# VFD_PSU_V2.net
KiCad netlist of a schematic drawn in EAGLE
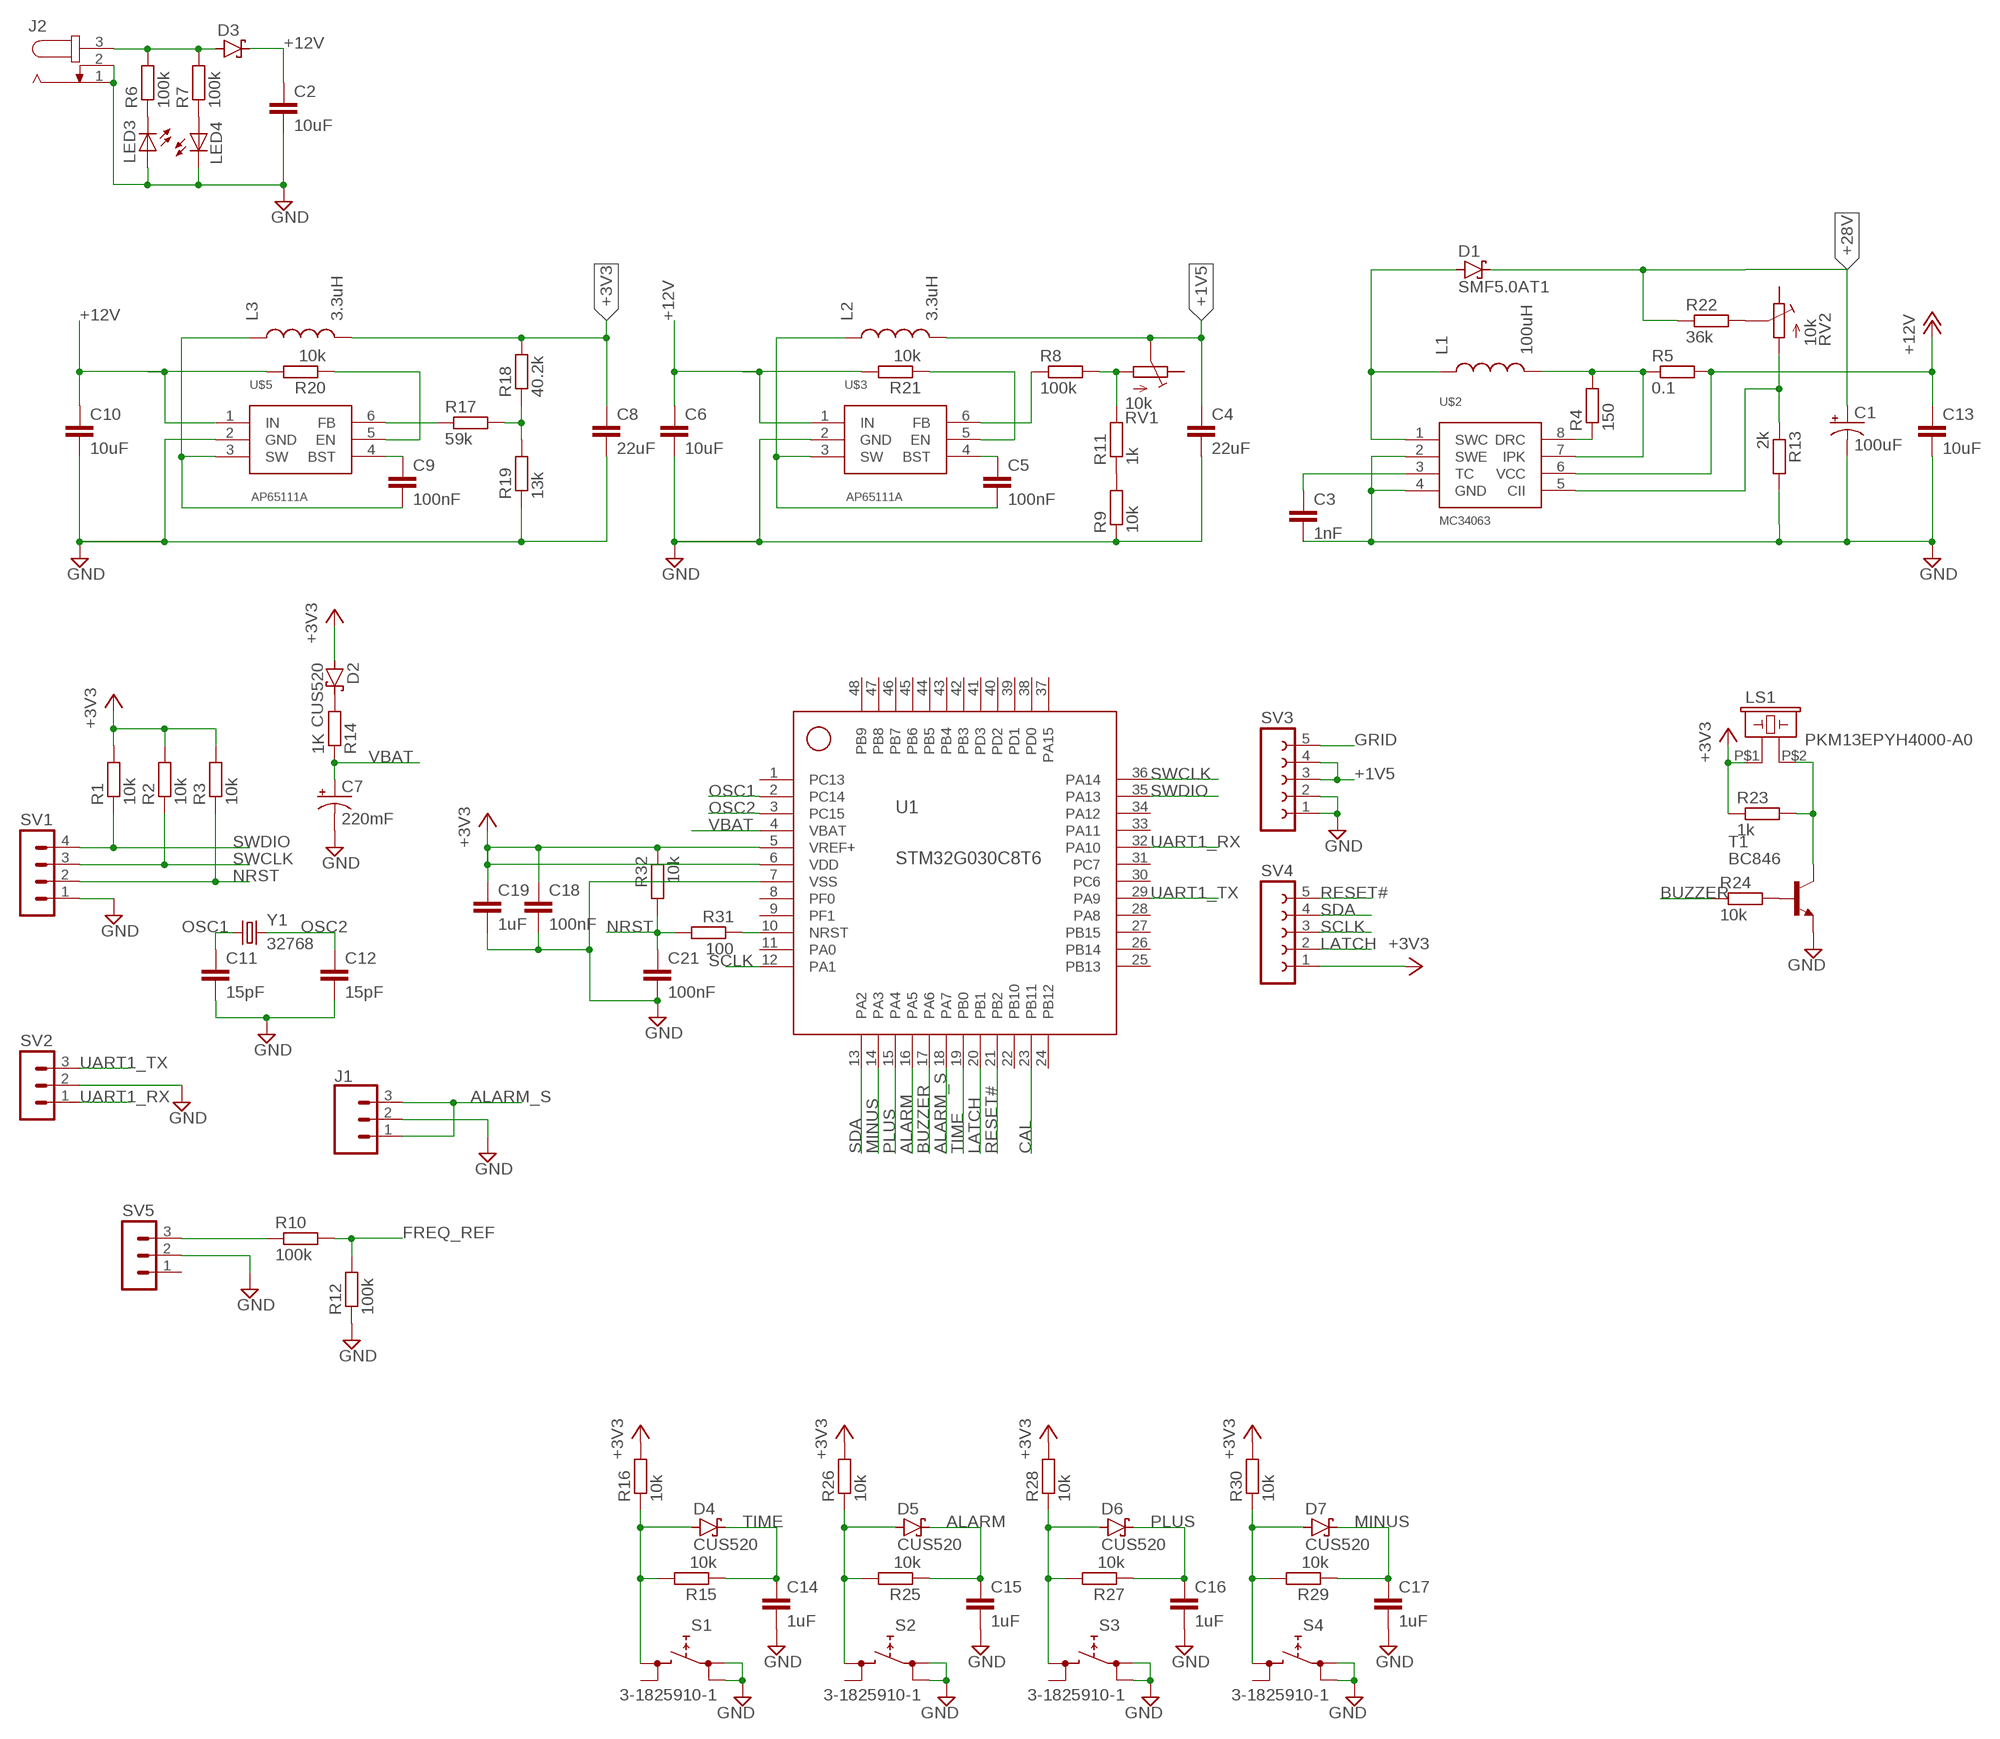
[diagram p0: schematic, sheet 1]

(export (version "E")
  (design (tool "Eeschema 10.0.6"))
  (components
    (comp (ref "C1")
      (value "100uF")
      (footprint "eagle-import:PANASONIC_C")
      (libsource (lib "eagle-import") (part "22UF-POLAR-PANASONIC_C-35V-20%"))
    )
    (comp (ref "C2")
      (value "10uF")
      (footprint "eagle-import:C0805")
      (libsource (lib "eagle-import") (part "C-EUC0805"))
    )
    (comp (ref "C3")
      (value "1nF")
      (footprint "eagle-import:C0603")
      (libsource (lib "eagle-import") (part "C-EUC0603"))
    )
    (comp (ref "C4")
      (value "22uF")
      (footprint "eagle-import:C0805")
      (libsource (lib "eagle-import") (part "C-EUC0805"))
    )
    (comp (ref "C5")
      (value "100nF")
      (footprint "eagle-import:C0603")
      (libsource (lib "eagle-import") (part "C-EUC0603"))
    )
    (comp (ref "C6")
      (value "10uF")
      (footprint "eagle-import:C0805")
      (libsource (lib "eagle-import") (part "C-EUC0805"))
    )
    (comp (ref "C7")
      (value "220mF")
      (footprint "eagle-import:4.8-COINCELL-SCAP")
      (libsource (lib "eagle-import") (part "DSK-3R3H224U-HL"))
    )
    (comp (ref "C8")
      (value "22uF")
      (footprint "eagle-import:C0805")
      (libsource (lib "eagle-import") (part "C-EUC0805"))
    )
    (comp (ref "C9")
      (value "100nF")
      (footprint "eagle-import:C0603")
      (libsource (lib "eagle-import") (part "C-EUC0603"))
    )
    (comp (ref "C10")
      (value "10uF")
      (footprint "eagle-import:C0805")
      (libsource (lib "eagle-import") (part "C-EUC0805"))
    )
    (comp (ref "C11")
      (value "15pF")
      (footprint "eagle-import:C0402")
      (libsource (lib "eagle-import") (part "resistor_348_C-EUC0402"))
    )
    (comp (ref "C12")
      (value "15pF")
      (footprint "eagle-import:C0402")
      (libsource (lib "eagle-import") (part "resistor_348_C-EUC0402"))
    )
    (comp (ref "C13")
      (value "10uF")
      (footprint "eagle-import:C0805")
      (libsource (lib "eagle-import") (part "C-EUC0805"))
    )
    (comp (ref "C14")
      (value "1uF")
      (footprint "eagle-import:C0603")
      (libsource (lib "eagle-import") (part "C-EUC0603"))
    )
    (comp (ref "C15")
      (value "1uF")
      (footprint "eagle-import:C0603")
      (libsource (lib "eagle-import") (part "C-EUC0603"))
    )
    (comp (ref "C16")
      (value "1uF")
      (footprint "eagle-import:C0603")
      (libsource (lib "eagle-import") (part "C-EUC0603"))
    )
    (comp (ref "C17")
      (value "1uF")
      (footprint "eagle-import:C0603")
      (libsource (lib "eagle-import") (part "C-EUC0603"))
    )
    (comp (ref "C18")
      (value "100nF")
      (footprint "eagle-import:C0603")
      (libsource (lib "eagle-import") (part "C-EUC0603"))
    )
    (comp (ref "C19")
      (value "1uF")
      (footprint "eagle-import:C0603")
      (libsource (lib "eagle-import") (part "C-EUC0603"))
    )
    (comp (ref "C21")
      (value "100nF")
      (footprint "eagle-import:C0603")
      (libsource (lib "eagle-import") (part "C-EUC0603"))
    )
    (comp (ref "D1")
      (value "SMF5.0AT1")
      (footprint "eagle-import:SOD123FL")
      (libsource (lib "eagle-import") (part "SMF5.0AT1"))
    )
    (comp (ref "D2")
      (value "CUS520")
      (footprint "eagle-import:SOD323_ST")
      (libsource (lib "eagle-import") (part "BAT60J"))
    )
    (comp (ref "D3")
      (value "SCHOTTKY-DIODESMD")
      (footprint "eagle-import:SMB")
      (libsource (lib "eagle-import") (part "SCHOTTKY-DIODESMD"))
    )
    (comp (ref "D4")
      (value "CUS520")
      (footprint "eagle-import:SOD323_ST")
      (libsource (lib "eagle-import") (part "BAT60J"))
    )
    (comp (ref "D5")
      (value "CUS520")
      (footprint "eagle-import:SOD323_ST")
      (libsource (lib "eagle-import") (part "BAT60J"))
    )
    (comp (ref "D6")
      (value "CUS520")
      (footprint "eagle-import:SOD323_ST")
      (libsource (lib "eagle-import") (part "BAT60J"))
    )
    (comp (ref "D7")
      (value "CUS520")
      (footprint "eagle-import:SOD323_ST")
      (libsource (lib "eagle-import") (part "BAT60J"))
    )
    (comp (ref "J1")
      (value "CONN_03JST-PTH-NS")
      (footprint "eagle-import:JST-3-PTH-NS")
      (libsource (lib "eagle-import") (part "CONN_03JST-PTH-NS"))
    )
    (comp (ref "J2")
      (value "JACK-PLUG0")
      (footprint "eagle-import:SPC4077")
      (libsource (lib "eagle-import") (part "JACK-PLUG0"))
    )
    (comp (ref "L1")
      (value "100uH")
      (footprint "eagle-import:2-SMD")
      (libsource (lib "eagle-import") (part "ETQ-P5M101YGK"))
    )
    (comp (ref "L2")
      (value "3.3uH")
      (footprint "eagle-import:1008")
      (libsource (lib "eagle-import") (part "VFD_L1008"))
    )
    (comp (ref "L3")
      (value "3.3uH")
      (footprint "eagle-import:1008")
      (libsource (lib "eagle-import") (part "L1008"))
    )
    (comp (ref "LED3")
      (value "LEDSMT1206")
      (footprint "eagle-import:1206")
      (libsource (lib "eagle-import") (part "LEDSMT1206"))
    )
    (comp (ref "LED4")
      (value "LEDSMT1206")
      (footprint "eagle-import:1206")
      (libsource (lib "eagle-import") (part "LEDSMT1206"))
    )
    (comp (ref "LS1")
      (value "PKM13EPYH4000-A0")
      (footprint "eagle-import:PKM13EPYH4000-A0")
      (libsource (lib "eagle-import") (part "PKM13EPYH4000-A0"))
    )
    (comp (ref "R1")
      (value "10k")
      (footprint "eagle-import:R0603")
      (libsource (lib "eagle-import") (part "resistor_348_R-EU_R0603"))
    )
    (comp (ref "R2")
      (value "10k")
      (footprint "eagle-import:R0603")
      (libsource (lib "eagle-import") (part "resistor_348_R-EU_R0603"))
    )
    (comp (ref "R3")
      (value "10k")
      (footprint "eagle-import:R0603")
      (libsource (lib "eagle-import") (part "resistor_348_R-EU_R0603"))
    )
    (comp (ref "R4")
      (value "150")
      (footprint "eagle-import:R0603")
      (libsource (lib "eagle-import") (part "resistor_348_R-EU_R0603"))
    )
    (comp (ref "R5")
      (value "0.1")
      (footprint "eagle-import:R0805")
      (libsource (lib "eagle-import") (part "R-EU_R0805"))
    )
    (comp (ref "R6")
      (value "100k")
      (footprint "eagle-import:R0603")
      (libsource (lib "eagle-import") (part "resistor_348_R-EU_R0603"))
    )
    (comp (ref "R7")
      (value "100k")
      (footprint "eagle-import:R0603")
      (libsource (lib "eagle-import") (part "resistor_348_R-EU_R0603"))
    )
    (comp (ref "R8")
      (value "100k")
      (footprint "eagle-import:R0603")
      (libsource (lib "eagle-import") (part "resistor_348_R-EU_R0603"))
    )
    (comp (ref "R9")
      (value "10k")
      (footprint "eagle-import:R0603")
      (libsource (lib "eagle-import") (part "resistor_348_R-EU_R0603"))
    )
    (comp (ref "R10")
      (value "100k")
      (footprint "eagle-import:R0603")
      (libsource (lib "eagle-import") (part "resistor_348_R-EU_R0603"))
    )
    (comp (ref "R11")
      (value "1k")
      (footprint "eagle-import:R0603")
      (libsource (lib "eagle-import") (part "resistor_348_R-EU_R0603"))
    )
    (comp (ref "R12")
      (value "100k")
      (footprint "eagle-import:R0603")
      (libsource (lib "eagle-import") (part "resistor_348_R-EU_R0603"))
    )
    (comp (ref "R13")
      (value "2k")
      (footprint "eagle-import:R0603")
      (libsource (lib "eagle-import") (part "resistor_348_R-EU_R0603"))
    )
    (comp (ref "R14")
      (value "1K")
      (footprint "eagle-import:R0603")
      (libsource (lib "eagle-import") (part "resistor_348_R-EU_R0603"))
    )
    (comp (ref "R15")
      (value "10k")
      (footprint "eagle-import:R0603")
      (libsource (lib "eagle-import") (part "resistor_348_R-EU_R0603"))
    )
    (comp (ref "R16")
      (value "10k")
      (footprint "eagle-import:R0603")
      (libsource (lib "eagle-import") (part "resistor_348_R-EU_R0603"))
    )
    (comp (ref "R17")
      (value "59k")
      (footprint "eagle-import:R0603")
      (libsource (lib "eagle-import") (part "resistor_348_R-EU_R0603"))
    )
    (comp (ref "R18")
      (value "40.2k")
      (footprint "eagle-import:R0603")
      (libsource (lib "eagle-import") (part "resistor_348_R-EU_R0603"))
    )
    (comp (ref "R19")
      (value "13k")
      (footprint "eagle-import:R0603")
      (libsource (lib "eagle-import") (part "resistor_348_R-EU_R0603"))
    )
    (comp (ref "R20")
      (value "10k")
      (footprint "eagle-import:R0603")
      (libsource (lib "eagle-import") (part "resistor_348_R-EU_R0603"))
    )
    (comp (ref "R21")
      (value "10k")
      (footprint "eagle-import:R0603")
      (libsource (lib "eagle-import") (part "resistor_348_R-EU_R0603"))
    )
    (comp (ref "R22")
      (value "36k")
      (footprint "eagle-import:R0603")
      (libsource (lib "eagle-import") (part "resistor_348_R-EU_R0603"))
    )
    (comp (ref "R23")
      (value "1k")
      (footprint "eagle-import:R0603")
      (libsource (lib "eagle-import") (part "resistor_348_R-EU_R0603"))
    )
    (comp (ref "R24")
      (value "10k")
      (footprint "eagle-import:R0603")
      (libsource (lib "eagle-import") (part "resistor_348_R-EU_R0603"))
    )
    (comp (ref "R25")
      (value "10k")
      (footprint "eagle-import:R0603")
      (libsource (lib "eagle-import") (part "resistor_348_R-EU_R0603"))
    )
    (comp (ref "R26")
      (value "10k")
      (footprint "eagle-import:R0603")
      (libsource (lib "eagle-import") (part "resistor_348_R-EU_R0603"))
    )
    (comp (ref "R27")
      (value "10k")
      (footprint "eagle-import:R0603")
      (libsource (lib "eagle-import") (part "resistor_348_R-EU_R0603"))
    )
    (comp (ref "R28")
      (value "10k")
      (footprint "eagle-import:R0603")
      (libsource (lib "eagle-import") (part "resistor_348_R-EU_R0603"))
    )
    (comp (ref "R29")
      (value "10k")
      (footprint "eagle-import:R0603")
      (libsource (lib "eagle-import") (part "resistor_348_R-EU_R0603"))
    )
    (comp (ref "R30")
      (value "10k")
      (footprint "eagle-import:R0603")
      (libsource (lib "eagle-import") (part "resistor_348_R-EU_R0603"))
    )
    (comp (ref "R31")
      (value "100")
      (footprint "eagle-import:R0603")
      (libsource (lib "eagle-import") (part "resistor_348_R-EU_R0603"))
    )
    (comp (ref "R32")
      (value "10k")
      (footprint "eagle-import:R0603")
      (libsource (lib "eagle-import") (part "resistor_348_R-EU_R0603"))
    )
    (comp (ref "RV1")
      (value "10k")
      (footprint "eagle-import:TC33X-2")
      (libsource (lib "eagle-import") (part "TC33X-2"))
    )
    (comp (ref "RV2")
      (value "10k")
      (footprint "eagle-import:TC33X-2")
      (libsource (lib "eagle-import") (part "TC33X-2"))
    )
    (comp (ref "S1")
      (value "3-1825910-1")
      (footprint "eagle-import:PANASONISWITCH")
      (libsource (lib "eagle-import") (part "PANASONICSWITCH"))
    )
    (comp (ref "S2")
      (value "3-1825910-1")
      (footprint "eagle-import:PANASONISWITCH")
      (libsource (lib "eagle-import") (part "PANASONICSWITCH"))
    )
    (comp (ref "S3")
      (value "3-1825910-1")
      (footprint "eagle-import:PANASONISWITCH")
      (libsource (lib "eagle-import") (part "PANASONICSWITCH"))
    )
    (comp (ref "S4")
      (value "3-1825910-1")
      (footprint "eagle-import:PANASONISWITCH")
      (libsource (lib "eagle-import") (part "PANASONICSWITCH"))
    )
    (comp (ref "SV1")
      (value "MA04-1")
      (footprint "eagle-import:MA04-1")
      (libsource (lib "eagle-import") (part "MA04-1"))
    )
    (comp (ref "SV2")
      (value "MA03-1")
      (footprint "eagle-import:MA03-1")
      (libsource (lib "eagle-import") (part "MA03-1"))
    )
    (comp (ref "SV3")
      (value "FE05W")
      (footprint "eagle-import:FE05W")
      (libsource (lib "eagle-import") (part "FE05W"))
    )
    (comp (ref "SV4")
      (value "FE05W")
      (footprint "eagle-import:FE05W")
      (libsource (lib "eagle-import") (part "FE05W"))
    )
    (comp (ref "SV5")
      (value "MA03-1")
      (footprint "eagle-import:MA03-1")
      (libsource (lib "eagle-import") (part "MA03-1"))
    )
    (comp (ref "T1")
      (value "BC846")
      (footprint "eagle-import:SOT23")
      (libsource (lib "eagle-import") (part "BC846"))
    )
    (comp (ref "U$2")
      (value "MC34063")
      (footprint "eagle-import:SO08")
      (libsource (lib "eagle-import") (part "MC34063"))
    )
    (comp (ref "U$3")
      (value "AP65111A")
      (footprint "eagle-import:TSOT23-6")
      (libsource (lib "eagle-import") (part "VFD_AP65111A"))
    )
    (comp (ref "U$5")
      (value "AP65111A")
      (footprint "eagle-import:TSOT23-6")
      (libsource (lib "eagle-import") (part "AP65111A"))
    )
    (comp (ref "U1")
      (value "STM32G030C8T6")
      (footprint "eagle-import:LQFP48")
      (libsource (lib "eagle-import") (part "STM32G030C8T6"))
    )
    (comp (ref "Y1")
      (value "32768")
      (footprint "eagle-import:2-SMD-NO-LEAD-Q")
      (libsource (lib "eagle-import") (part "FC-135"))
    )
  )
  (nets
    (net (code "1") (name "+1V5") (class "Default")
      (node (ref "C4") (pin "1") (pinfunction "1_1") (pintype "passive"))
      (node (ref "L2") (pin "P$2") (pinfunction "2_P$2") (pintype "passive"))
      (node (ref "RV1") (pin "P$2") (pinfunction "S_P$2") (pintype "passive"))
      (node (ref "SV3") (pin "3") (pinfunction "3_3") (pintype "passive"))
      (node (ref "SV3") (pin "4") (pinfunction "4_4") (pintype "passive"))
    )
    (net (code "2") (name "+3V3") (class "Default")
      (node (ref "C18") (pin "1") (pinfunction "1_1") (pintype "passive"))
      (node (ref "C19") (pin "1") (pinfunction "1_1") (pintype "passive"))
      (node (ref "C8") (pin "1") (pinfunction "1_1") (pintype "passive"))
      (node (ref "D2") (pin "A") (pinfunction "A_A") (pintype "passive"))
      (node (ref "L3") (pin "P$2") (pinfunction "2_P$2") (pintype "passive"))
      (node (ref "LS1") (pin "P$1") (pinfunction "1_P$1") (pintype "passive"))
      (node (ref "R1") (pin "2") (pinfunction "2_2") (pintype "passive"))
      (node (ref "R16") (pin "2") (pinfunction "2_2") (pintype "passive"))
      (node (ref "R18") (pin "2") (pinfunction "2_2") (pintype "passive"))
      (node (ref "R2") (pin "2") (pinfunction "2_2") (pintype "passive"))
      (node (ref "R23") (pin "1") (pinfunction "1_1") (pintype "passive"))
      (node (ref "R26") (pin "2") (pinfunction "2_2") (pintype "passive"))
      (node (ref "R28") (pin "2") (pinfunction "2_2") (pintype "passive"))
      (node (ref "R3") (pin "2") (pinfunction "2_2") (pintype "passive"))
      (node (ref "R30") (pin "2") (pinfunction "2_2") (pintype "passive"))
      (node (ref "R32") (pin "1") (pinfunction "1_1") (pintype "passive"))
      (node (ref "SV4") (pin "1") (pinfunction "1_1") (pintype "passive"))
      (node (ref "U1") (pin "5") (pinfunction "VREF+_5") (pintype "power_in"))
      (node (ref "U1") (pin "6") (pinfunction "VDD_6") (pintype "power_in"))
    )
    (net (code "3") (name "+12V") (class "Default")
      (node (ref "C10") (pin "1") (pinfunction "1_1") (pintype "passive"))
      (node (ref "C13") (pin "1") (pinfunction "1_1") (pintype "passive"))
      (node (ref "C2") (pin "1") (pinfunction "1_1") (pintype "passive"))
      (node (ref "C6") (pin "1") (pinfunction "1_1") (pintype "passive"))
      (node (ref "D3") (pin "C") (pinfunction "C_C") (pintype "passive"))
      (node (ref "R20") (pin "2") (pinfunction "2_2") (pintype "passive"))
      (node (ref "R21") (pin "2") (pinfunction "2_2") (pintype "passive"))
      (node (ref "R5") (pin "2") (pinfunction "2_2") (pintype "passive"))
      (node (ref "U$2") (pin "6") (pinfunction "VCC_6") (pintype "bidirectional"))
      (node (ref "U$3") (pin "1") (pinfunction "IN_1") (pintype "bidirectional"))
      (node (ref "U$5") (pin "1") (pinfunction "IN_1") (pintype "bidirectional"))
    )
    (net (code "4") (name "+28V") (class "Default")
      (node (ref "C1") (pin "+") (pinfunction "+_+") (pintype "passive"))
      (node (ref "D1") (pin "C") (pinfunction "C_C") (pintype "passive"))
      (node (ref "R22") (pin "1") (pinfunction "1_1") (pintype "passive"))
    )
    (net (code "5") (name "/ALARM") (class "Default")
      (node (ref "C15") (pin "1") (pinfunction "1_1") (pintype "passive"))
      (node (ref "D5") (pin "C") (pinfunction "C_C") (pintype "passive"))
      (node (ref "R25") (pin "1") (pinfunction "1_1") (pintype "passive"))
      (node (ref "U1") (pin "16") (pinfunction "PA5_16") (pintype "bidirectional"))
    )
    (net (code "6") (name "/ALARM_S") (class "Default")
      (node (ref "J1") (pin "1") (pinfunction "1_1") (pintype "passive"))
      (node (ref "J1") (pin "3") (pinfunction "3_3") (pintype "passive"))
      (node (ref "U1") (pin "18") (pinfunction "PA7_18") (pintype "bidirectional"))
    )
    (net (code "7") (name "/BUZZER") (class "Default")
      (node (ref "R24") (pin "1") (pinfunction "1_1") (pintype "passive"))
      (node (ref "U1") (pin "17") (pinfunction "PA6_17") (pintype "bidirectional"))
    )
    (net (code "8") (name "/CAL") (class "Default")
      (node (ref "U1") (pin "23") (pinfunction "PB11_23") (pintype "bidirectional"))
    )
    (net (code "9") (name "/FREQ_REF") (class "Default")
      (node (ref "R10") (pin "2") (pinfunction "2_2") (pintype "passive"))
      (node (ref "R12") (pin "2") (pinfunction "2_2") (pintype "passive"))
    )
    (net (code "10") (name "/GRID") (class "Default")
      (node (ref "SV3") (pin "5") (pinfunction "5_5") (pintype "passive"))
    )
    (net (code "11") (name "/LATCH") (class "Default")
      (node (ref "SV4") (pin "2") (pinfunction "2_2") (pintype "passive"))
      (node (ref "U1") (pin "20") (pinfunction "PB1_20") (pintype "bidirectional"))
    )
    (net (code "12") (name "/MINUS") (class "Default")
      (node (ref "C17") (pin "1") (pinfunction "1_1") (pintype "passive"))
      (node (ref "D7") (pin "C") (pinfunction "C_C") (pintype "passive"))
      (node (ref "R29") (pin "1") (pinfunction "1_1") (pintype "passive"))
      (node (ref "U1") (pin "14") (pinfunction "PA3_14") (pintype "bidirectional"))
    )
    (net (code "13") (name "/NRST") (class "Default")
      (node (ref "C21") (pin "1") (pinfunction "1_1") (pintype "passive"))
      (node (ref "R3") (pin "1") (pinfunction "1_1") (pintype "passive"))
      (node (ref "R31") (pin "2") (pinfunction "2_2") (pintype "passive"))
      (node (ref "R32") (pin "2") (pinfunction "2_2") (pintype "passive"))
      (node (ref "SV1") (pin "2") (pinfunction "2_2") (pintype "passive"))
    )
    (net (code "14") (name "/OSC1") (class "Default")
      (node (ref "C11") (pin "1") (pinfunction "1_1") (pintype "passive"))
      (node (ref "U1") (pin "2") (pinfunction "PC14_2") (pintype "bidirectional"))
      (node (ref "Y1") (pin "P$1") (pinfunction "1_P$1") (pintype "passive"))
    )
    (net (code "15") (name "/OSC2") (class "Default")
      (node (ref "C12") (pin "1") (pinfunction "1_1") (pintype "passive"))
      (node (ref "U1") (pin "3") (pinfunction "PC15_3") (pintype "bidirectional"))
      (node (ref "Y1") (pin "P$2") (pinfunction "2_P$2") (pintype "passive"))
    )
    (net (code "16") (name "/PLUS") (class "Default")
      (node (ref "C16") (pin "1") (pinfunction "1_1") (pintype "passive"))
      (node (ref "D6") (pin "C") (pinfunction "C_C") (pintype "passive"))
      (node (ref "R27") (pin "1") (pinfunction "1_1") (pintype "passive"))
      (node (ref "U1") (pin "15") (pinfunction "PA4_15") (pintype "bidirectional"))
    )
    (net (code "17") (name "/RESET#") (class "Default")
      (node (ref "SV4") (pin "5") (pinfunction "5_5") (pintype "passive"))
      (node (ref "U1") (pin "21") (pinfunction "PB2_21") (pintype "bidirectional"))
    )
    (net (code "18") (name "/SCLK") (class "Default")
      (node (ref "SV4") (pin "3") (pinfunction "3_3") (pintype "passive"))
      (node (ref "U1") (pin "12") (pinfunction "PA1_12") (pintype "bidirectional"))
    )
    (net (code "19") (name "/SDA") (class "Default")
      (node (ref "SV4") (pin "4") (pinfunction "4_4") (pintype "passive"))
      (node (ref "U1") (pin "13") (pinfunction "PA2_13") (pintype "bidirectional"))
    )
    (net (code "20") (name "/SWCLK") (class "Default")
      (node (ref "R2") (pin "1") (pinfunction "1_1") (pintype "passive"))
      (node (ref "SV1") (pin "3") (pinfunction "3_3") (pintype "passive"))
      (node (ref "U1") (pin "36") (pinfunction "PA14_36") (pintype "bidirectional"))
    )
    (net (code "21") (name "/SWDIO") (class "Default")
      (node (ref "R1") (pin "1") (pinfunction "1_1") (pintype "passive"))
      (node (ref "SV1") (pin "4") (pinfunction "4_4") (pintype "passive"))
      (node (ref "U1") (pin "35") (pinfunction "PA13_35") (pintype "bidirectional"))
    )
    (net (code "22") (name "/TIME") (class "Default")
      (node (ref "C14") (pin "1") (pinfunction "1_1") (pintype "passive"))
      (node (ref "D4") (pin "C") (pinfunction "C_C") (pintype "passive"))
      (node (ref "R15") (pin "1") (pinfunction "1_1") (pintype "passive"))
      (node (ref "U1") (pin "19") (pinfunction "PB0_19") (pintype "bidirectional"))
    )
    (net (code "23") (name "/UART1_RX") (class "Default")
      (node (ref "SV2") (pin "1") (pinfunction "1_1") (pintype "passive"))
      (node (ref "U1") (pin "32") (pinfunction "PA10_32") (pintype "bidirectional"))
    )
    (net (code "24") (name "/UART1_TX") (class "Default")
      (node (ref "SV2") (pin "3") (pinfunction "3_3") (pintype "passive"))
      (node (ref "U1") (pin "29") (pinfunction "PA9_29") (pintype "bidirectional"))
    )
    (net (code "25") (name "/VBAT") (class "Default")
      (node (ref "C7") (pin "P$1") (pinfunction "+_P$1") (pintype "passive"))
      (node (ref "R14") (pin "1") (pinfunction "1_1") (pintype "passive"))
      (node (ref "U1") (pin "4") (pinfunction "VBAT_4") (pintype "power_in"))
    )
    (net (code "26") (name "GND") (class "Default")
      (node (ref "C1") (pin "-") (pinfunction "-_-") (pintype "passive"))
      (node (ref "C10") (pin "2") (pinfunction "2_2") (pintype "passive"))
      (node (ref "C11") (pin "2") (pinfunction "2_2") (pintype "passive"))
      (node (ref "C12") (pin "2") (pinfunction "2_2") (pintype "passive"))
      (node (ref "C13") (pin "2") (pinfunction "2_2") (pintype "passive"))
      (node (ref "C14") (pin "2") (pinfunction "2_2") (pintype "passive"))
      (node (ref "C15") (pin "2") (pinfunction "2_2") (pintype "passive"))
      (node (ref "C16") (pin "2") (pinfunction "2_2") (pintype "passive"))
      (node (ref "C17") (pin "2") (pinfunction "2_2") (pintype "passive"))
      (node (ref "C18") (pin "2") (pinfunction "2_2") (pintype "passive"))
      (node (ref "C19") (pin "2") (pinfunction "2_2") (pintype "passive"))
      (node (ref "C2") (pin "2") (pinfunction "2_2") (pintype "passive"))
      (node (ref "C21") (pin "2") (pinfunction "2_2") (pintype "passive"))
      (node (ref "C3") (pin "2") (pinfunction "2_2") (pintype "passive"))
      (node (ref "C4") (pin "2") (pinfunction "2_2") (pintype "passive"))
      (node (ref "C6") (pin "2") (pinfunction "2_2") (pintype "passive"))
      (node (ref "C7") (pin "P$2") (pinfunction "-_P$2") (pintype "passive"))
      (node (ref "C8") (pin "2") (pinfunction "2_2") (pintype "passive"))
      (node (ref "J1") (pin "2") (pinfunction "2_2") (pintype "passive"))
      (node (ref "J2") (pin "1") (pinfunction "1_1") (pintype "passive"))
      (node (ref "J2") (pin "2") (pinfunction "2_2") (pintype "passive"))
      (node (ref "LED3") (pin "A") (pinfunction "A_A") (pintype "passive"))
      (node (ref "LED4") (pin "C") (pinfunction "C_C") (pintype "passive"))
      (node (ref "R12") (pin "1") (pinfunction "1_1") (pintype "passive"))
      (node (ref "R13") (pin "2") (pinfunction "2_2") (pintype "passive"))
      (node (ref "R19") (pin "1") (pinfunction "1_1") (pintype "passive"))
      (node (ref "R9") (pin "1") (pinfunction "1_1") (pintype "passive"))
      (node (ref "S1") (pin "P$1") (pinfunction "0_P$1") (pintype "passive"))
      (node (ref "S1") (pin "P$2") (pinfunction "0_P$2") (pintype "passive"))
      (node (ref "S2") (pin "P$1") (pinfunction "0_P$1") (pintype "passive"))
      (node (ref "S2") (pin "P$2") (pinfunction "0_P$2") (pintype "passive"))
      (node (ref "S3") (pin "P$1") (pinfunction "0_P$1") (pintype "passive"))
      (node (ref "S3") (pin "P$2") (pinfunction "0_P$2") (pintype "passive"))
      (node (ref "S4") (pin "P$1") (pinfunction "0_P$1") (pintype "passive"))
      (node (ref "S4") (pin "P$2") (pinfunction "0_P$2") (pintype "passive"))
      (node (ref "SV1") (pin "1") (pinfunction "1_1") (pintype "passive"))
      (node (ref "SV2") (pin "2") (pinfunction "2_2") (pintype "passive"))
      (node (ref "SV3") (pin "1") (pinfunction "1_1") (pintype "passive"))
      (node (ref "SV3") (pin "2") (pinfunction "2_2") (pintype "passive"))
      (node (ref "SV5") (pin "2") (pinfunction "2_2") (pintype "passive"))
      (node (ref "T1") (pin "2") (pinfunction "E_2") (pintype "passive"))
      (node (ref "U$2") (pin "2") (pinfunction "SWE_2") (pintype "bidirectional"))
      (node (ref "U$2") (pin "4") (pinfunction "GND_4") (pintype "bidirectional"))
      (node (ref "U$3") (pin "2") (pinfunction "GND_2") (pintype "bidirectional"))
      (node (ref "U$5") (pin "2") (pinfunction "GND_2") (pintype "bidirectional"))
      (node (ref "U1") (pin "7") (pinfunction "VSS_7") (pintype "power_in"))
    )
    (net (code "27") (name "Net-(D2-PadC)") (class "Default")
      (node (ref "D2") (pin "C") (pinfunction "C_C") (pintype "passive"))
      (node (ref "R14") (pin "2") (pinfunction "2_2") (pintype "passive"))
    )
    (net (code "28") (name "Net-(D3-PadA)") (class "Default")
      (node (ref "D3") (pin "A") (pinfunction "A_A") (pintype "passive"))
      (node (ref "J2") (pin "3") (pinfunction "3_3") (pintype "passive"))
      (node (ref "R6") (pin "2") (pinfunction "2_2") (pintype "passive"))
      (node (ref "R7") (pin "2") (pinfunction "2_2") (pintype "passive"))
    )
    (net (code "29") (name "Net-(D4-PadA)") (class "Default")
      (node (ref "D4") (pin "A") (pinfunction "A_A") (pintype "passive"))
      (node (ref "R15") (pin "2") (pinfunction "2_2") (pintype "passive"))
      (node (ref "R16") (pin "1") (pinfunction "1_1") (pintype "passive"))
      (node (ref "S1") (pin "P$3") (pinfunction "1_P$3") (pintype "passive"))
    )
    (net (code "30") (name "Net-(D5-PadA)") (class "Default")
      (node (ref "D5") (pin "A") (pinfunction "A_A") (pintype "passive"))
      (node (ref "R25") (pin "2") (pinfunction "2_2") (pintype "passive"))
      (node (ref "R26") (pin "1") (pinfunction "1_1") (pintype "passive"))
      (node (ref "S2") (pin "P$3") (pinfunction "1_P$3") (pintype "passive"))
    )
    (net (code "31") (name "Net-(D6-PadA)") (class "Default")
      (node (ref "D6") (pin "A") (pinfunction "A_A") (pintype "passive"))
      (node (ref "R27") (pin "2") (pinfunction "2_2") (pintype "passive"))
      (node (ref "R28") (pin "1") (pinfunction "1_1") (pintype "passive"))
      (node (ref "S3") (pin "P$3") (pinfunction "1_P$3") (pintype "passive"))
    )
    (net (code "32") (name "Net-(D7-PadA)") (class "Default")
      (node (ref "D7") (pin "A") (pinfunction "A_A") (pintype "passive"))
      (node (ref "R29") (pin "2") (pinfunction "2_2") (pintype "passive"))
      (node (ref "R30") (pin "1") (pinfunction "1_1") (pintype "passive"))
      (node (ref "S4") (pin "P$3") (pinfunction "1_P$3") (pintype "passive"))
    )
    (net (code "33") (name "Net-(L1-1)") (class "Default")
      (node (ref "D1") (pin "A") (pinfunction "A_A") (pintype "passive"))
      (node (ref "L1") (pin "P$1") (pinfunction "1_P$1") (pintype "passive"))
      (node (ref "U$2") (pin "1") (pinfunction "SWC_1") (pintype "bidirectional"))
    )
    (net (code "34") (name "Net-(L1-2)") (class "Default")
      (node (ref "L1") (pin "P$2") (pinfunction "2_P$2") (pintype "passive"))
      (node (ref "R4") (pin "2") (pinfunction "2_2") (pintype "passive"))
      (node (ref "R5") (pin "1") (pinfunction "1_1") (pintype "passive"))
      (node (ref "U$2") (pin "7") (pinfunction "IPK_7") (pintype "bidirectional"))
    )
    (net (code "35") (name "Net-(L2-1)") (class "Default")
      (node (ref "C5") (pin "2") (pinfunction "2_2") (pintype "passive"))
      (node (ref "L2") (pin "P$1") (pinfunction "1_P$1") (pintype "passive"))
      (node (ref "U$3") (pin "3") (pinfunction "SW_3") (pintype "bidirectional"))
    )
    (net (code "36") (name "Net-(L3-1)") (class "Default")
      (node (ref "C9") (pin "2") (pinfunction "2_2") (pintype "passive"))
      (node (ref "L3") (pin "P$1") (pinfunction "1_P$1") (pintype "passive"))
      (node (ref "U$5") (pin "3") (pinfunction "SW_3") (pintype "bidirectional"))
    )
    (net (code "37") (name "Net-(LED3-PadC)") (class "Default")
      (node (ref "LED3") (pin "C") (pinfunction "C_C") (pintype "passive"))
      (node (ref "R6") (pin "1") (pinfunction "1_1") (pintype "passive"))
    )
    (net (code "38") (name "Net-(LED4-PadA)") (class "Default")
      (node (ref "LED4") (pin "A") (pinfunction "A_A") (pintype "passive"))
      (node (ref "R7") (pin "1") (pinfunction "1_1") (pintype "passive"))
    )
    (net (code "39") (name "Net-(LS1-2)") (class "Default")
      (node (ref "LS1") (pin "P$2") (pinfunction "2_P$2") (pintype "passive"))
      (node (ref "R23") (pin "2") (pinfunction "2_2") (pintype "passive"))
      (node (ref "T1") (pin "3") (pinfunction "C_3") (pintype "passive"))
    )
    (net (code "40") (name "Net-(R10-Pad1)") (class "Default")
      (node (ref "R10") (pin "1") (pinfunction "1_1") (pintype "passive"))
      (node (ref "SV5") (pin "3") (pinfunction "3_3") (pintype "passive"))
    )
    (net (code "41") (name "Net-(R11-Pad1)") (class "Default")
      (node (ref "R11") (pin "1") (pinfunction "1_1") (pintype "passive"))
      (node (ref "R9") (pin "2") (pinfunction "2_2") (pintype "passive"))
    )
    (net (code "42") (name "Net-(R17-Pad2)") (class "Default")
      (node (ref "R17") (pin "2") (pinfunction "2_2") (pintype "passive"))
      (node (ref "R18") (pin "1") (pinfunction "1_1") (pintype "passive"))
      (node (ref "R19") (pin "2") (pinfunction "2_2") (pintype "passive"))
    )
    (net (code "43") (name "Net-(RV1-E)") (class "Default")
      (node (ref "R11") (pin "2") (pinfunction "2_2") (pintype "passive"))
      (node (ref "R8") (pin "2") (pinfunction "2_2") (pintype "passive"))
      (node (ref "RV1") (pin "P$1") (pinfunction "E_P$1") (pintype "passive"))
    )
    (net (code "44") (name "Net-(RV2-E)") (class "Default")
      (node (ref "R13") (pin "1") (pinfunction "1_1") (pintype "passive"))
      (node (ref "RV2") (pin "P$1") (pinfunction "E_P$1") (pintype "passive"))
      (node (ref "U$2") (pin "5") (pinfunction "CII_5") (pintype "bidirectional"))
    )
    (net (code "45") (name "Net-(RV2-S)") (class "Default")
      (node (ref "R22") (pin "2") (pinfunction "2_2") (pintype "passive"))
      (node (ref "RV2") (pin "P$2") (pinfunction "S_P$2") (pintype "passive"))
    )
    (net (code "46") (name "Net-(T1-B)") (class "Default")
      (node (ref "R24") (pin "2") (pinfunction "2_2") (pintype "passive"))
      (node (ref "T1") (pin "1") (pinfunction "B_1") (pintype "passive"))
    )
    (net (code "47") (name "Net-(U$2-DRC)") (class "Default")
      (node (ref "R4") (pin "1") (pinfunction "1_1") (pintype "passive"))
      (node (ref "U$2") (pin "8") (pinfunction "DRC_8") (pintype "bidirectional"))
    )
    (net (code "48") (name "Net-(U$2-TC)") (class "Default")
      (node (ref "C3") (pin "1") (pinfunction "1_1") (pintype "passive"))
      (node (ref "U$2") (pin "3") (pinfunction "TC_3") (pintype "bidirectional"))
    )
    (net (code "49") (name "Net-(U$3-BST)") (class "Default")
      (node (ref "C5") (pin "1") (pinfunction "1_1") (pintype "passive"))
      (node (ref "U$3") (pin "4") (pinfunction "BST_4") (pintype "bidirectional"))
    )
    (net (code "50") (name "Net-(U$3-EN)") (class "Default")
      (node (ref "R21") (pin "1") (pinfunction "1_1") (pintype "passive"))
      (node (ref "U$3") (pin "5") (pinfunction "EN_5") (pintype "bidirectional"))
    )
    (net (code "51") (name "Net-(U$3-FB)") (class "Default")
      (node (ref "R8") (pin "1") (pinfunction "1_1") (pintype "passive"))
      (node (ref "U$3") (pin "6") (pinfunction "FB_6") (pintype "bidirectional"))
    )
    (net (code "52") (name "Net-(U$5-BST)") (class "Default")
      (node (ref "C9") (pin "1") (pinfunction "1_1") (pintype "passive"))
      (node (ref "U$5") (pin "4") (pinfunction "BST_4") (pintype "bidirectional"))
    )
    (net (code "53") (name "Net-(U$5-EN)") (class "Default")
      (node (ref "R20") (pin "1") (pinfunction "1_1") (pintype "passive"))
      (node (ref "U$5") (pin "5") (pinfunction "EN_5") (pintype "bidirectional"))
    )
    (net (code "54") (name "Net-(U$5-FB)") (class "Default")
      (node (ref "R17") (pin "1") (pinfunction "1_1") (pintype "passive"))
      (node (ref "U$5") (pin "6") (pinfunction "FB_6") (pintype "bidirectional"))
    )
    (net (code "55") (name "Net-(U1-NRST)") (class "Default")
      (node (ref "R31") (pin "1") (pinfunction "1_1") (pintype "passive"))
      (node (ref "U1") (pin "10") (pinfunction "NRST_10") (pintype "bidirectional"))
    )
    (net (code "56") (name "unconnected-(RV1-A-PadP$3)") (class "Default")
      (node (ref "RV1") (pin "P$3") (pinfunction "A_P$3") (pintype "passive"))
    )
    (net (code "57") (name "unconnected-(RV2-A-PadP$3)") (class "Default")
      (node (ref "RV2") (pin "P$3") (pinfunction "A_P$3") (pintype "passive"))
    )
    (net (code "58") (name "unconnected-(S1-1-PadP$4)") (class "Default")
      (node (ref "S1") (pin "P$4") (pinfunction "1_P$4") (pintype "passive"))
    )
    (net (code "59") (name "unconnected-(S2-1-PadP$4)") (class "Default")
      (node (ref "S2") (pin "P$4") (pinfunction "1_P$4") (pintype "passive"))
    )
    (net (code "60") (name "unconnected-(S3-1-PadP$4)") (class "Default")
      (node (ref "S3") (pin "P$4") (pinfunction "1_P$4") (pintype "passive"))
    )
    (net (code "61") (name "unconnected-(S4-1-PadP$4)") (class "Default")
      (node (ref "S4") (pin "P$4") (pinfunction "1_P$4") (pintype "passive"))
    )
    (net (code "62") (name "unconnected-(SV5-Pad1)") (class "Default")
      (node (ref "SV5") (pin "1") (pinfunction "1_1") (pintype "passive"))
    )
    (net (code "63") (name "unconnected-(U1-PA0-Pad11)") (class "Default")
      (node (ref "U1") (pin "11") (pinfunction "PA0_11") (pintype "bidirectional"))
    )
    (net (code "64") (name "unconnected-(U1-PA8-Pad28)") (class "Default")
      (node (ref "U1") (pin "28") (pinfunction "PA8_28") (pintype "bidirectional"))
    )
    (net (code "65") (name "unconnected-(U1-PA11-Pad33)") (class "Default")
      (node (ref "U1") (pin "33") (pinfunction "PA11_33") (pintype "bidirectional"))
    )
    (net (code "66") (name "unconnected-(U1-PA12-Pad34)") (class "Default")
      (node (ref "U1") (pin "34") (pinfunction "PA12_34") (pintype "bidirectional"))
    )
    (net (code "67") (name "unconnected-(U1-PA15-Pad37)") (class "Default")
      (node (ref "U1") (pin "37") (pinfunction "PA15_37") (pintype "bidirectional"))
    )
    (net (code "68") (name "unconnected-(U1-PB3-Pad42)") (class "Default")
      (node (ref "U1") (pin "42") (pinfunction "PB3_42") (pintype "bidirectional"))
    )
    (net (code "69") (name "unconnected-(U1-PB4-Pad43)") (class "Default")
      (node (ref "U1") (pin "43") (pinfunction "PB4_43") (pintype "bidirectional"))
    )
    (net (code "70") (name "unconnected-(U1-PB5-Pad44)") (class "Default")
      (node (ref "U1") (pin "44") (pinfunction "PB5_44") (pintype "bidirectional"))
    )
    (net (code "71") (name "unconnected-(U1-PB6-Pad45)") (class "Default")
      (node (ref "U1") (pin "45") (pinfunction "PB6_45") (pintype "bidirectional"))
    )
    (net (code "72") (name "unconnected-(U1-PB7-Pad46)") (class "Default")
      (node (ref "U1") (pin "46") (pinfunction "PB7_46") (pintype "bidirectional"))
    )
    (net (code "73") (name "unconnected-(U1-PB8-Pad47)") (class "Default")
      (node (ref "U1") (pin "47") (pinfunction "PB8_47") (pintype "bidirectional"))
    )
    (net (code "74") (name "unconnected-(U1-PB9-Pad48)") (class "Default")
      (node (ref "U1") (pin "48") (pinfunction "PB9_48") (pintype "bidirectional"))
    )
    (net (code "75") (name "unconnected-(U1-PB10-Pad22)") (class "Default")
      (node (ref "U1") (pin "22") (pinfunction "PB10_22") (pintype "bidirectional"))
    )
    (net (code "76") (name "unconnected-(U1-PB12-Pad24)") (class "Default")
      (node (ref "U1") (pin "24") (pinfunction "PB12_24") (pintype "bidirectional"))
    )
    (net (code "77") (name "unconnected-(U1-PB13-Pad25)") (class "Default")
      (node (ref "U1") (pin "25") (pinfunction "PB13_25") (pintype "bidirectional"))
    )
    (net (code "78") (name "unconnected-(U1-PB14-Pad26)") (class "Default")
      (node (ref "U1") (pin "26") (pinfunction "PB14_26") (pintype "bidirectional"))
    )
    (net (code "79") (name "unconnected-(U1-PB15-Pad27)") (class "Default")
      (node (ref "U1") (pin "27") (pinfunction "PB15_27") (pintype "bidirectional"))
    )
    (net (code "80") (name "unconnected-(U1-PC6-Pad30)") (class "Default")
      (node (ref "U1") (pin "30") (pinfunction "PC6_30") (pintype "bidirectional"))
    )
    (net (code "81") (name "unconnected-(U1-PC7-Pad31)") (class "Default")
      (node (ref "U1") (pin "31") (pinfunction "PC7_31") (pintype "bidirectional"))
    )
    (net (code "82") (name "unconnected-(U1-PC13-Pad1)") (class "Default")
      (node (ref "U1") (pin "1") (pinfunction "PC13_1") (pintype "bidirectional"))
    )
    (net (code "83") (name "unconnected-(U1-PD0-Pad38)") (class "Default")
      (node (ref "U1") (pin "38") (pinfunction "PD0_38") (pintype "bidirectional"))
    )
    (net (code "84") (name "unconnected-(U1-PD1-Pad39)") (class "Default")
      (node (ref "U1") (pin "39") (pinfunction "PD1_39") (pintype "bidirectional"))
    )
    (net (code "85") (name "unconnected-(U1-PD2-Pad40)") (class "Default")
      (node (ref "U1") (pin "40") (pinfunction "PD2_40") (pintype "bidirectional"))
    )
    (net (code "86") (name "unconnected-(U1-PD3-Pad41)") (class "Default")
      (node (ref "U1") (pin "41") (pinfunction "PD3_41") (pintype "bidirectional"))
    )
    (net (code "87") (name "unconnected-(U1-PF0-Pad8)") (class "Default")
      (node (ref "U1") (pin "8") (pinfunction "PF0_8") (pintype "bidirectional"))
    )
    (net (code "88") (name "unconnected-(U1-PF1-Pad9)") (class "Default")
      (node (ref "U1") (pin "9") (pinfunction "PF1_9") (pintype "bidirectional"))
    )
  )
)
